# PIC32.net
KiCad netlist of a schematic drawn in Altium Designer
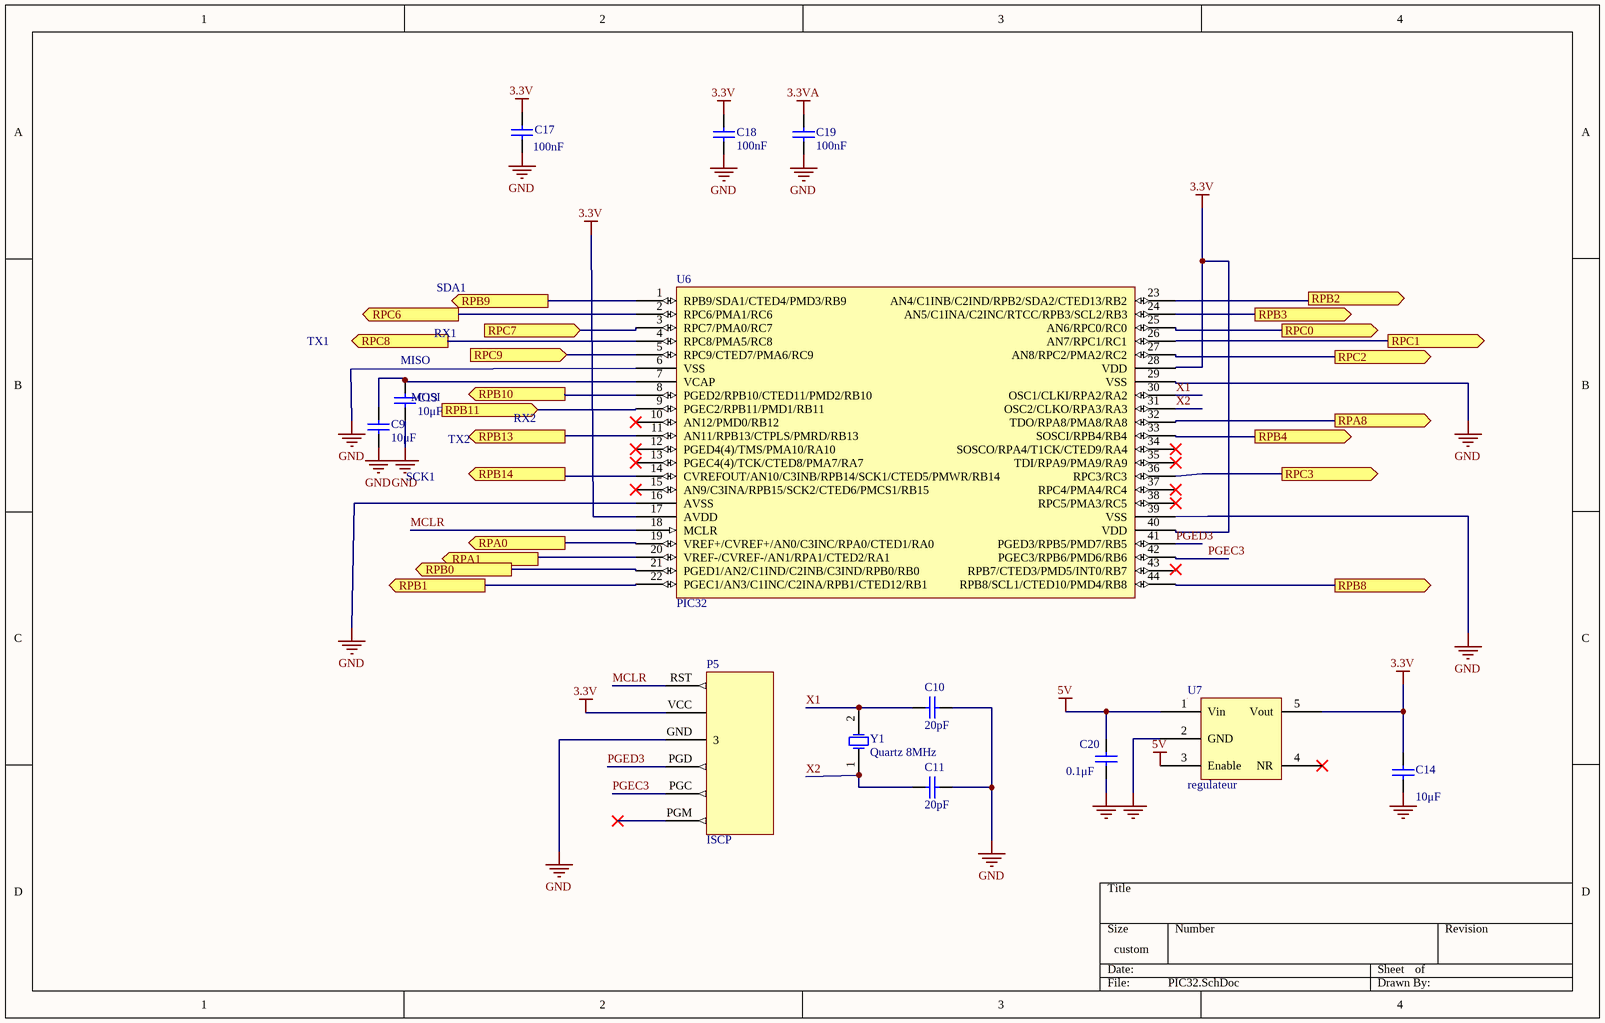
[diagram p0: PIC32.SchDoc]

(export (version "E")
  (design (tool "Eeschema 10.0.6"))
  (components
    (comp (ref "C9")
      (value "10μF")
      (footprint "cond")
      (description "Capacitor")
      (fields (field (name "Comment") "Cap") (field (name "PUBLISHER") "Altium Limited"))
      (libsource (lib "Miscellaneous Devices") (part "Cap"))
    )
    (comp (ref "C10")
      (value "20pF")
      (footprint "cond")
      (description "Capacitor")
      (fields (field (name "Comment") "Cap") (field (name "PUBLISHER") "Altium Limited"))
      (libsource (lib "Miscellaneous Devices") (part "Cap"))
    )
    (comp (ref "C11")
      (value "20pF")
      (footprint "cond")
      (description "Capacitor")
      (fields (field (name "Comment") "Cap") (field (name "PUBLISHER") "Altium Limited"))
      (libsource (lib "Miscellaneous Devices") (part "Cap"))
    )
    (comp (ref "C13")
      (value "10μF")
      (footprint "cond")
      (description "Capacitor")
      (fields (field (name "Comment") "Cap") (field (name "PUBLISHER") "Altium Limited"))
      (libsource (lib "Miscellaneous Devices") (part "Cap"))
    )
    (comp (ref "C14")
      (value "10μF")
      (footprint "cond")
      (description "Capacitor")
      (fields (field (name "Comment") "Cap") (field (name "PUBLISHER") "Altium Limited"))
      (libsource (lib "Miscellaneous Devices") (part "Cap"))
    )
    (comp (ref "C17")
      (value "100nF")
      (footprint "cond")
      (description "Capacitor")
      (fields (field (name "Comment") "Cap") (field (name "PUBLISHER") "Altium Limited"))
      (libsource (lib "Miscellaneous Devices") (part "Cap"))
    )
    (comp (ref "C18")
      (value "100nF")
      (footprint "cond")
      (description "Capacitor")
      (fields (field (name "Comment") "Cap") (field (name "PUBLISHER") "Altium Limited"))
      (libsource (lib "Miscellaneous Devices") (part "Cap"))
    )
    (comp (ref "C19")
      (value "100nF")
      (footprint "cond")
      (description "Capacitor")
      (fields (field (name "Comment") "Cap") (field (name "PUBLISHER") "Altium Limited"))
      (libsource (lib "Miscellaneous Devices") (part "Cap"))
    )
    (comp (ref "C20")
      (value "0.1μF")
      (footprint "cond")
      (description "Capacitor")
      (fields (field (name "Comment") "Cap") (field (name "PUBLISHER") "Altium Limited"))
      (libsource (lib "Miscellaneous Devices") (part "Cap"))
    )
    (comp (ref "P5") (value "ISCP") (footprint "ISCP") (libsource (lib "Schlib1") (part "ISCP")))
    (comp (ref "U6") (value "PIC32") (footprint "PIC32") (libsource (lib "Schlib1") (part "PIC32")))
    (comp (ref "U7")
      (value "regulateur")
      (footprint "regulateur")
      (libsource (lib "Schlib1") (part "regulateur"))
    )
    (comp (ref "Y1")
      (value "Quartz 8MHz")
      (footprint "quartz")
      (description "Crystal Oscillator")
      (fields (field (name "PUBLISHER") "Altium Limited"))
      (libsource (lib "Miscellaneous Devices") (part "XTAL"))
    )
  )
  (nets
    (net (code "1") (name "/MCLR") (class "Default")
      (node (ref "P5") (pin "RST") (pinfunction "1_RST") (pintype "output"))
      (node (ref "U6") (pin "18") (pinfunction "MCLR_18") (pintype "input"))
    )
    (net (code "2") (name "/PGEC3") (class "Default")
      (node (ref "P5") (pin "PGC") (pinfunction "5_PGC") (pintype "output"))
      (node (ref "U6") (pin "42") (pinfunction "PGEC3/RPB6/PMD6/RB6_42") (pintype "bidirectional"))
    )
    (net (code "3") (name "/PGED3") (class "Default")
      (node (ref "P5") (pin "PGD") (pinfunction "4_PGD") (pintype "output"))
      (node (ref "U6") (pin "41") (pinfunction "PGED3/RPB5/PMD7/RB5_41") (pintype "bidirectional"))
    )
    (net (code "4") (name "/RPA0") (class "Default")
      (node (ref "U6") (pin "19") (pinfunction "VREF+/CVREF+/AN0/C3INC/RPA0/CTED1/RA0_19") (pintype "bidirectional"))
    )
    (net (code "5") (name "/RPA1") (class "Default")
      (node (ref "U6") (pin "20") (pinfunction "VREF-/CVREF-/AN1/RPA1/CTED2/RA1_20") (pintype "bidirectional"))
    )
    (net (code "6") (name "/RPA8") (class "Default")
      (node (ref "U6") (pin "32") (pinfunction "TDO/RPA8/PMA8/RA8_32") (pintype "bidirectional"))
    )
    (net (code "7") (name "/RPB0") (class "Default")
      (node (ref "U6") (pin "21") (pinfunction "PGED1/AN2/C1IND/C2INB/C3IND/RPB0/RB0_21") (pintype "bidirectional"))
    )
    (net (code "8") (name "/RPB1") (class "Default")
      (node (ref "U6") (pin "22") (pinfunction "PGEC1/AN3/C1INC/C2INA/RPB1/CTED12/RB1_22") (pintype "bidirectional"))
    )
    (net (code "9") (name "/RPB2") (class "Default")
      (node (ref "U6") (pin "23") (pinfunction "AN4/C1INB/C2IND/RPB2/SDA2/CTED13/RB2_23") (pintype "bidirectional"))
    )
    (net (code "10") (name "/RPB3") (class "Default")
      (node (ref "U6") (pin "24") (pinfunction "AN5/C1INA/C2INC/RTCC/RPB3/SCL2/RB3_24") (pintype "bidirectional"))
    )
    (net (code "11") (name "/RPB4") (class "Default")
      (node (ref "U6") (pin "33") (pinfunction "SOSCI/RPB4/RB4_33") (pintype "bidirectional"))
    )
    (net (code "12") (name "/RPB8") (class "Default")
      (node (ref "U6") (pin "44") (pinfunction "RPB8/SCL1/CTED10/PMD4/RB8_44") (pintype "bidirectional"))
    )
    (net (code "13") (name "/RPB9") (class "Default")
      (node (ref "U6") (pin "1") (pinfunction "RPB9/SDA1/CTED4/PMD3/RB9_1") (pintype "bidirectional"))
    )
    (net (code "14") (name "/RPB10") (class "Default")
      (node (ref "U6") (pin "8") (pinfunction "PGED2/RPB10/CTED11/PMD2/RB10_8") (pintype "bidirectional"))
    )
    (net (code "15") (name "/RPB11") (class "Default")
      (node (ref "U6") (pin "9") (pinfunction "PGEC2/RPB11/PMD1/RB11_9") (pintype "bidirectional"))
    )
    (net (code "16") (name "/RPB13") (class "Default")
      (node (ref "U6") (pin "11") (pinfunction "AN11/RPB13/CTPLS/PMRD/RB13_11") (pintype "bidirectional"))
    )
    (net (code "17") (name "/RPB14") (class "Default")
      (node (ref "U6") (pin "14") (pinfunction "CVREFOUT/AN10/C3INB/RPB14/SCK1/CTED5/PMWR/RB14_14") (pintype "bidirectional"))
    )
    (net (code "18") (name "/RPC0") (class "Default")
      (node (ref "U6") (pin "25") (pinfunction "AN6/RPC0/RC0_25") (pintype "bidirectional"))
    )
    (net (code "20") (name "/RPC1") (class "Default")
      (node (ref "U6") (pin "26") (pinfunction "AN7/RPC1/RC1_26") (pintype "bidirectional"))
    )
    (net (code "21") (name "/RPC2") (class "Default")
      (node (ref "U6") (pin "27") (pinfunction "AN8/RPC2/PMA2/RC2_27") (pintype "bidirectional"))
    )
    (net (code "22") (name "/RPC3") (class "Default")
      (node (ref "U6") (pin "36") (pinfunction "RPC3/RC3_36") (pintype "bidirectional"))
    )
    (net (code "23") (name "/RPC6") (class "Default")
      (node (ref "U6") (pin "2") (pinfunction "RPC6/PMA1/RC6_2") (pintype "bidirectional"))
    )
    (net (code "24") (name "/RPC7") (class "Default")
      (node (ref "U6") (pin "3") (pinfunction "RPC7/PMA0/RC7_3") (pintype "bidirectional"))
    )
    (net (code "25") (name "/RPC8") (class "Default")
      (node (ref "U6") (pin "4") (pinfunction "RPC8/PMA5/RC8_4") (pintype "bidirectional"))
    )
    (net (code "26") (name "/RPC9") (class "Default")
      (node (ref "U6") (pin "5") (pinfunction "RPC9/CTED7/PMA6/RC9_5") (pintype "bidirectional"))
    )
    (net (code "27") (name "/X1") (class "Default")
      (node (ref "C10") (pin "2") (pinfunction "2_2") (pintype "passive"))
      (node (ref "U6") (pin "30") (pinfunction "OSC1/CLKI/RPA2/RA2_30") (pintype "bidirectional"))
      (node (ref "Y1") (pin "2") (pinfunction "OSC2_2") (pintype "passive"))
    )
    (net (code "28") (name "/X2") (class "Default")
      (node (ref "C11") (pin "2") (pinfunction "2_2") (pintype "passive"))
      (node (ref "U6") (pin "31") (pinfunction "OSC2/CLKO/RPA3/RA3_31") (pintype "bidirectional"))
      (node (ref "Y1") (pin "1") (pinfunction "OSC1_1") (pintype "passive"))
    )
    (net (code "29") (name "3.3V") (class "Default")
      (node (ref "C14") (pin "2") (pinfunction "2_2") (pintype "passive"))
      (node (ref "C17") (pin "2") (pinfunction "2_2") (pintype "passive"))
      (node (ref "C18") (pin "1") (pinfunction "1_1") (pintype "passive"))
      (node (ref "P5") (pin "VCC") (pinfunction "2_VCC") (pintype "passive"))
      (node (ref "U6") (pin "17") (pinfunction "AVDD_17") (pintype "passive"))
      (node (ref "U6") (pin "40") (pinfunction "VDD_40") (pintype "passive"))
      (node (ref "U7") (pin "5") (pinfunction "Vout_5") (pintype "passive"))
    )
    (net (code "30") (name "3.3VA") (class "Default")
      (node (ref "C19") (pin "1") (pinfunction "1_1") (pintype "passive"))
    )
    (net (code "31") (name "5V") (class "Default")
      (node (ref "C20") (pin "2") (pinfunction "2_2") (pintype "passive"))
      (node (ref "U7") (pin "1") (pinfunction "Vin_1") (pintype "power_in"))
      (node (ref "U7") (pin "3") (pinfunction "Enable_3") (pintype "passive"))
    )
    (net (code "32") (name "GND") (class "Default")
      (node (ref "C10") (pin "1") (pinfunction "1_1") (pintype "passive"))
      (node (ref "C11") (pin "1") (pinfunction "1_1") (pintype "passive"))
      (node (ref "C13") (pin "2") (pinfunction "2_2") (pintype "passive"))
      (node (ref "C14") (pin "1") (pinfunction "1_1") (pintype "passive"))
      (node (ref "C17") (pin "1") (pinfunction "1_1") (pintype "passive"))
      (node (ref "C18") (pin "2") (pinfunction "2_2") (pintype "passive"))
      (node (ref "C19") (pin "2") (pinfunction "2_2") (pintype "passive"))
      (node (ref "C20") (pin "1") (pinfunction "1_1") (pintype "passive"))
      (node (ref "C9") (pin "2") (pinfunction "2_2") (pintype "passive"))
      (node (ref "P5") (pin "GND") (pinfunction "3_GND") (pintype "passive"))
      (node (ref "U6") (pin "16") (pinfunction "AVSS_16") (pintype "passive"))
      (node (ref "U6") (pin "29") (pinfunction "VSS_29") (pintype "power_in"))
      (node (ref "U6") (pin "39") (pinfunction "VSS_39") (pintype "power_in"))
      (node (ref "U6") (pin "6") (pinfunction "VSS_6") (pintype "passive"))
      (node (ref "U7") (pin "2") (pinfunction "GND_2") (pintype "passive"))
    )
    (net (code "33") (name "Net-(U6-VCAP)") (class "Default")
      (node (ref "C13") (pin "1") (pinfunction "1_1") (pintype "passive"))
      (node (ref "C9") (pin "1") (pinfunction "1_1") (pintype "passive"))
      (node (ref "U6") (pin "7") (pinfunction "VCAP_7") (pintype "passive"))
    )
    (net (code "34") (name "unconnected-(P5-6-PadPGM)") (class "Default")
      (node (ref "P5") (pin "PGM") (pinfunction "6_PGM") (pintype "output+no_connect"))
    )
    (net (code "35") (name "unconnected-(U6-AN9{slash}C3INA{slash}RPB15{slash}SCK2{slash}CTED6{slash}PMCS1{slash}RB15-Pad15)") (class "Default")
      (node (ref "U6") (pin "15") (pinfunction "AN9/C3INA/RPB15/SCK2/CTED6/PMCS1/RB15_15") (pintype "bidirectional+no_connect"))
    )
    (net (code "36") (name "unconnected-(U6-AN12{slash}PMD0{slash}RB12-Pad10)") (class "Default")
      (node (ref "U6") (pin "10") (pinfunction "AN12/PMD0/RB12_10") (pintype "bidirectional+no_connect"))
    )
    (net (code "37") (name "unconnected-(U6-PGEC4(4){slash}TCK{slash}CTED8{slash}PMA7{slash}RA7-Pad13)") (class "Default")
      (node (ref "U6") (pin "13") (pinfunction "PGEC4(4)/TCK/CTED8/PMA7/RA7_13") (pintype "bidirectional+no_connect"))
    )
    (net (code "38") (name "unconnected-(U6-PGED4(4){slash}TMS{slash}PMA10{slash}RA10-Pad12)") (class "Default")
      (node (ref "U6") (pin "12") (pinfunction "PGED4(4)/TMS/PMA10/RA10_12") (pintype "bidirectional+no_connect"))
    )
    (net (code "39") (name "unconnected-(U6-RPB7{slash}CTED3{slash}PMD5{slash}INT0{slash}RB7-Pad43)") (class "Default")
      (node (ref "U6") (pin "43") (pinfunction "RPB7/CTED3/PMD5/INT0/RB7_43") (pintype "bidirectional"))
    )
    (net (code "40") (name "unconnected-(U6-RPC4{slash}PMA4{slash}RC4-Pad37)") (class "Default")
      (node (ref "U6") (pin "37") (pinfunction "RPC4/PMA4/RC4_37") (pintype "bidirectional+no_connect"))
    )
    (net (code "41") (name "unconnected-(U6-RPC5{slash}PMA3{slash}RC5-Pad38)") (class "Default")
      (node (ref "U6") (pin "38") (pinfunction "RPC5/PMA3/RC5_38") (pintype "bidirectional+no_connect"))
    )
    (net (code "42") (name "unconnected-(U6-SOSCO{slash}RPA4{slash}T1CK{slash}CTED9{slash}RA4-Pad34)") (class "Default")
      (node (ref "U6") (pin "34") (pinfunction "SOSCO/RPA4/T1CK/CTED9/RA4_34") (pintype "bidirectional+no_connect"))
    )
    (net (code "43") (name "unconnected-(U6-TDI{slash}RPA9{slash}PMA9{slash}RA9-Pad35)") (class "Default")
      (node (ref "U6") (pin "35") (pinfunction "TDI/RPA9/PMA9/RA9_35") (pintype "bidirectional+no_connect"))
    )
    (net (code "44") (name "unconnected-(U6-VDD-Pad28)") (class "Default")
      (node (ref "U6") (pin "28") (pinfunction "VDD_28") (pintype "passive"))
    )
    (net (code "45") (name "unconnected-(U7-NR-Pad4)") (class "Default")
      (node (ref "U7") (pin "4") (pinfunction "NR_4") (pintype "passive+no_connect"))
    )
  )
)
